# Ready-UNO.net
KiCad netlist of a schematic drawn in EAGLE
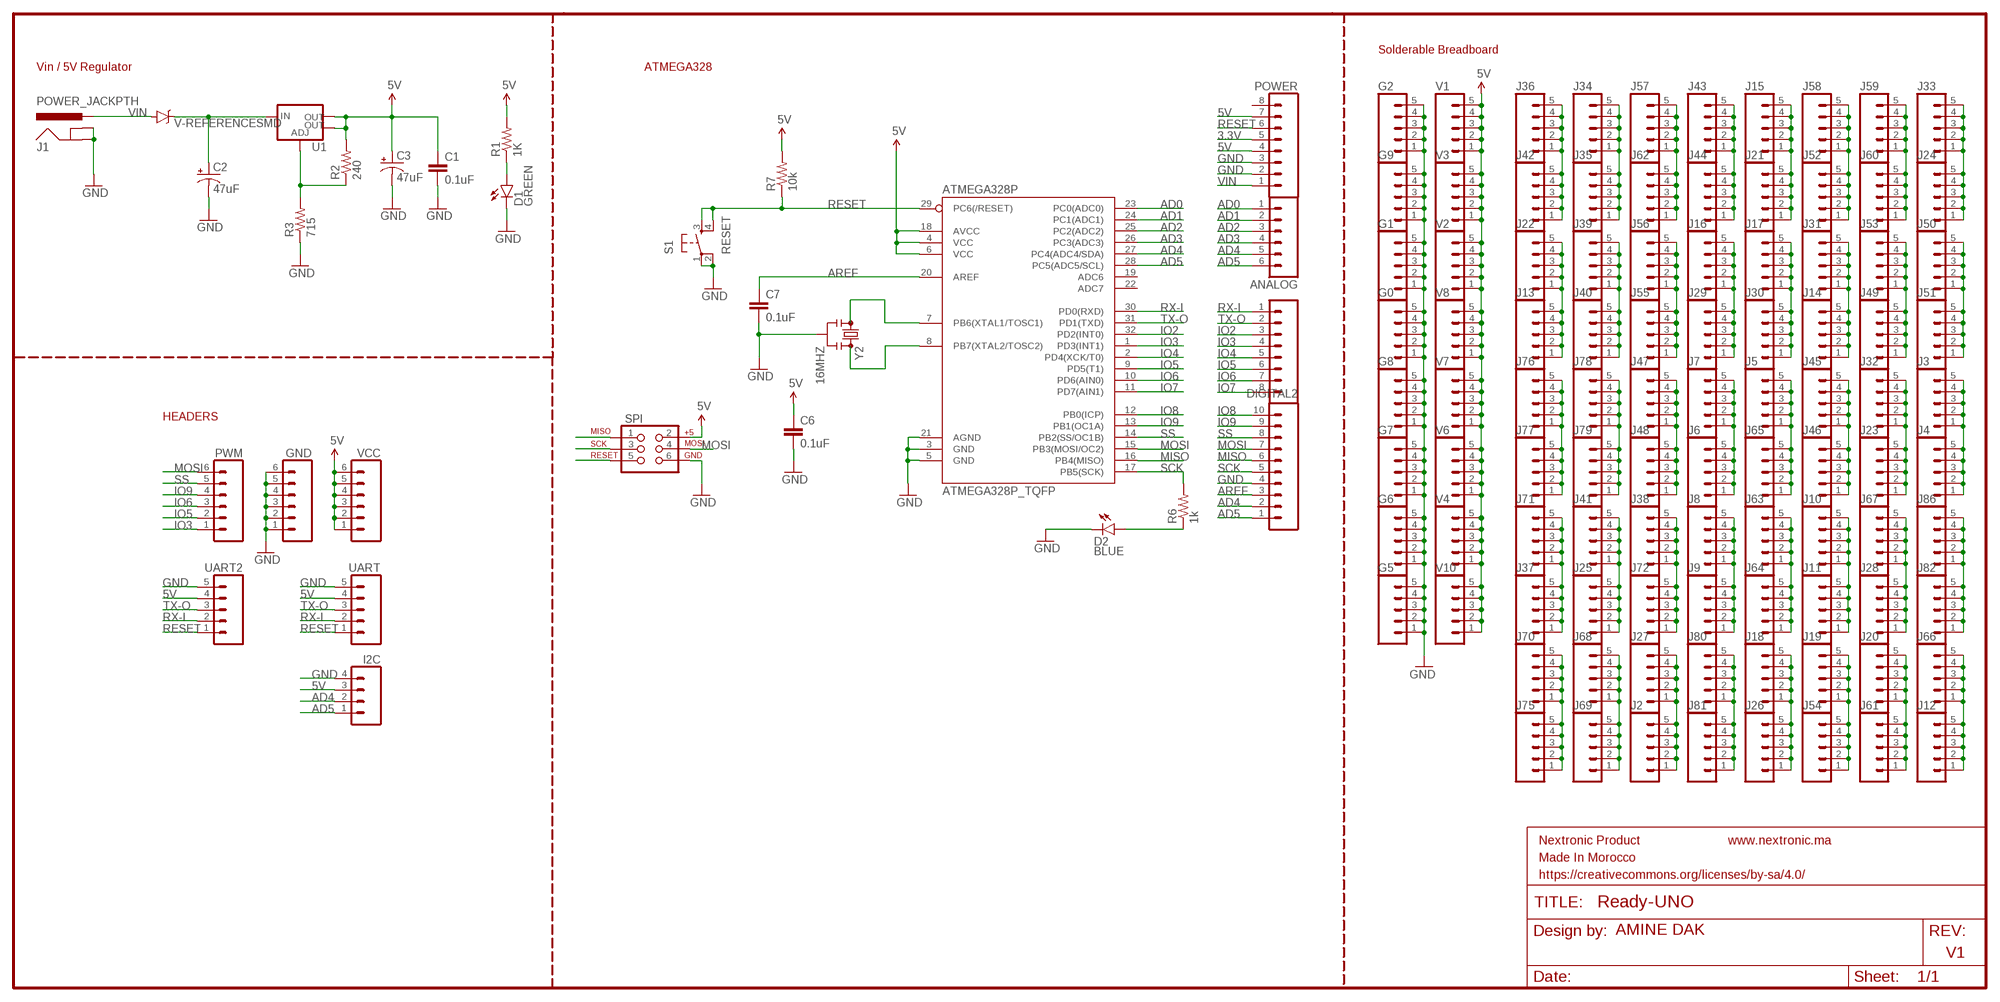
[diagram p0: schematic, sheet 1]

(export (version "E")
  (design (tool "Eeschema 10.0.6"))
  (components
    (comp (ref "ANALOG")
      (value "M06SILK_FEMALE_PTH")
      (footprint "eagle-import:1X06")
      (libsource (lib "eagle-import") (part "M06SILK_FEMALE_PTH"))
    )
    (comp (ref "ATMEGA328P")
      (value "ATMEGA328P_TQFP")
      (footprint "eagle-import:TQFP32-08")
      (libsource (lib "eagle-import") (part "ATMEGA328P_TQFP"))
    )
    (comp (ref "C1")
      (value "0.1uF")
      (footprint "eagle-import:0603-CAP")
      (libsource (lib "eagle-import") (part "CAP0603-CAP"))
    )
    (comp (ref "C2")
      (value "47uF")
      (footprint "eagle-import:PANASONIC_C")
      (libsource (lib "eagle-import") (part "CAP_POLC"))
    )
    (comp (ref "C3")
      (value "47uF")
      (footprint "eagle-import:PANASONIC_C")
      (libsource (lib "eagle-import") (part "CAP_POLC"))
    )
    (comp (ref "C6")
      (value "0.1uF")
      (footprint "eagle-import:0603-CAP")
      (libsource (lib "eagle-import") (part "CAP0603-CAP"))
    )
    (comp (ref "C7")
      (value "0.1uF")
      (footprint "eagle-import:0603-CAP")
      (libsource (lib "eagle-import") (part "CAP0603-CAP"))
    )
    (comp (ref "D1")
      (value "GREEN")
      (footprint "eagle-import:LED-1206")
      (libsource (lib "eagle-import") (part "LED-GREEN1206"))
    )
    (comp (ref "D2")
      (value "BLUE")
      (footprint "eagle-import:LED-1206")
      (libsource (lib "eagle-import") (part "LED-BLUE1206"))
    )
    (comp (ref "DIGITAL")
      (value "M08SILK_FEMALE_PTH")
      (footprint "eagle-import:1X08")
      (libsource (lib "eagle-import") (part "M08SILK_FEMALE_PTH"))
    )
    (comp (ref "DIGITAL2")
      (value "M10SILK_FEMALE_PTH")
      (footprint "eagle-import:1X10")
      (libsource (lib "eagle-import") (part "M10SILK_FEMALE_PTH"))
    )
    (comp (ref "G0")
      (value "M05PTH")
      (footprint "eagle-import:1X05")
      (libsource (lib "eagle-import") (part "M05PTH"))
    )
    (comp (ref "G1")
      (value "M05PTH")
      (footprint "eagle-import:1X05")
      (libsource (lib "eagle-import") (part "M05PTH"))
    )
    (comp (ref "G2")
      (value "M05PTH")
      (footprint "eagle-import:1X05")
      (libsource (lib "eagle-import") (part "M05PTH"))
    )
    (comp (ref "G5")
      (value "M05PTH")
      (footprint "eagle-import:1X05")
      (libsource (lib "eagle-import") (part "M05PTH"))
    )
    (comp (ref "G6")
      (value "M05PTH")
      (footprint "eagle-import:1X05")
      (libsource (lib "eagle-import") (part "M05PTH"))
    )
    (comp (ref "G7")
      (value "M05PTH")
      (footprint "eagle-import:1X05")
      (libsource (lib "eagle-import") (part "M05PTH"))
    )
    (comp (ref "G8")
      (value "M05PTH")
      (footprint "eagle-import:1X05")
      (libsource (lib "eagle-import") (part "M05PTH"))
    )
    (comp (ref "G9")
      (value "M05PTH")
      (footprint "eagle-import:1X05")
      (libsource (lib "eagle-import") (part "M05PTH"))
    )
    (comp (ref "GND")
      (value "M06SILK_FEMALE_PTH")
      (footprint "eagle-import:1X06")
      (libsource (lib "eagle-import") (part "M06SILK_FEMALE_PTH"))
    )
    (comp (ref "I2C")
      (value "M04PTH")
      (footprint "eagle-import:1X04")
      (libsource (lib "eagle-import") (part "M04PTH"))
    )
    (comp (ref "J1")
      (value "POWER_JACKPTH")
      (footprint "eagle-import:POWER_JACK_PTH")
      (libsource (lib "eagle-import") (part "POWER_JACKPTH"))
    )
    (comp (ref "J2")
      (value "M05PTH")
      (footprint "eagle-import:1X05")
      (libsource (lib "eagle-import") (part "M05PTH"))
    )
    (comp (ref "J3")
      (value "M05PTH")
      (footprint "eagle-import:1X05")
      (libsource (lib "eagle-import") (part "M05PTH"))
    )
    (comp (ref "J4")
      (value "M05PTH")
      (footprint "eagle-import:1X05")
      (libsource (lib "eagle-import") (part "M05PTH"))
    )
    (comp (ref "J5")
      (value "M05PTH")
      (footprint "eagle-import:1X05")
      (libsource (lib "eagle-import") (part "M05PTH"))
    )
    (comp (ref "J6")
      (value "M05PTH")
      (footprint "eagle-import:1X05")
      (libsource (lib "eagle-import") (part "M05PTH"))
    )
    (comp (ref "J7")
      (value "M05PTH")
      (footprint "eagle-import:1X05")
      (libsource (lib "eagle-import") (part "M05PTH"))
    )
    (comp (ref "J8")
      (value "M05PTH")
      (footprint "eagle-import:1X05")
      (libsource (lib "eagle-import") (part "M05PTH"))
    )
    (comp (ref "J9")
      (value "M05PTH")
      (footprint "eagle-import:1X05")
      (libsource (lib "eagle-import") (part "M05PTH"))
    )
    (comp (ref "J10")
      (value "M05PTH")
      (footprint "eagle-import:1X05")
      (libsource (lib "eagle-import") (part "M05PTH"))
    )
    (comp (ref "J11")
      (value "M05PTH")
      (footprint "eagle-import:1X05")
      (libsource (lib "eagle-import") (part "M05PTH"))
    )
    (comp (ref "J12")
      (value "M05PTH")
      (footprint "eagle-import:1X05")
      (libsource (lib "eagle-import") (part "M05PTH"))
    )
    (comp (ref "J13")
      (value "M05PTH")
      (footprint "eagle-import:1X05")
      (libsource (lib "eagle-import") (part "M05PTH"))
    )
    (comp (ref "J14")
      (value "M05PTH")
      (footprint "eagle-import:1X05")
      (libsource (lib "eagle-import") (part "M05PTH"))
    )
    (comp (ref "J15")
      (value "M05PTH")
      (footprint "eagle-import:1X05")
      (libsource (lib "eagle-import") (part "M05PTH"))
    )
    (comp (ref "J16")
      (value "M05PTH")
      (footprint "eagle-import:1X05")
      (libsource (lib "eagle-import") (part "M05PTH"))
    )
    (comp (ref "J17")
      (value "M05PTH")
      (footprint "eagle-import:1X05")
      (libsource (lib "eagle-import") (part "M05PTH"))
    )
    (comp (ref "J18")
      (value "M05PTH")
      (footprint "eagle-import:1X05")
      (libsource (lib "eagle-import") (part "M05PTH"))
    )
    (comp (ref "J19")
      (value "M05PTH")
      (footprint "eagle-import:1X05")
      (libsource (lib "eagle-import") (part "M05PTH"))
    )
    (comp (ref "J20")
      (value "M05PTH")
      (footprint "eagle-import:1X05")
      (libsource (lib "eagle-import") (part "M05PTH"))
    )
    (comp (ref "J21")
      (value "M05PTH")
      (footprint "eagle-import:1X05")
      (libsource (lib "eagle-import") (part "M05PTH"))
    )
    (comp (ref "J22")
      (value "M05PTH")
      (footprint "eagle-import:1X05")
      (libsource (lib "eagle-import") (part "M05PTH"))
    )
    (comp (ref "J23")
      (value "M05PTH")
      (footprint "eagle-import:1X05")
      (libsource (lib "eagle-import") (part "M05PTH"))
    )
    (comp (ref "J24")
      (value "M05PTH")
      (footprint "eagle-import:1X05")
      (libsource (lib "eagle-import") (part "M05PTH"))
    )
    (comp (ref "J25")
      (value "M05PTH")
      (footprint "eagle-import:1X05")
      (libsource (lib "eagle-import") (part "M05PTH"))
    )
    (comp (ref "J26")
      (value "M05PTH")
      (footprint "eagle-import:1X05")
      (libsource (lib "eagle-import") (part "M05PTH"))
    )
    (comp (ref "J27")
      (value "M05PTH")
      (footprint "eagle-import:1X05")
      (libsource (lib "eagle-import") (part "M05PTH"))
    )
    (comp (ref "J28")
      (value "M05PTH")
      (footprint "eagle-import:1X05")
      (libsource (lib "eagle-import") (part "M05PTH"))
    )
    (comp (ref "J29")
      (value "M05PTH")
      (footprint "eagle-import:1X05")
      (libsource (lib "eagle-import") (part "M05PTH"))
    )
    (comp (ref "J30")
      (value "M05PTH")
      (footprint "eagle-import:1X05")
      (libsource (lib "eagle-import") (part "M05PTH"))
    )
    (comp (ref "J31")
      (value "M05PTH")
      (footprint "eagle-import:1X05")
      (libsource (lib "eagle-import") (part "M05PTH"))
    )
    (comp (ref "J32")
      (value "M05PTH")
      (footprint "eagle-import:1X05")
      (libsource (lib "eagle-import") (part "M05PTH"))
    )
    (comp (ref "J33")
      (value "M05PTH")
      (footprint "eagle-import:1X05")
      (libsource (lib "eagle-import") (part "M05PTH"))
    )
    (comp (ref "J34")
      (value "M05PTH")
      (footprint "eagle-import:1X05")
      (libsource (lib "eagle-import") (part "M05PTH"))
    )
    (comp (ref "J35")
      (value "M05PTH")
      (footprint "eagle-import:1X05")
      (libsource (lib "eagle-import") (part "M05PTH"))
    )
    (comp (ref "J36")
      (value "M05PTH")
      (footprint "eagle-import:1X05")
      (libsource (lib "eagle-import") (part "M05PTH"))
    )
    (comp (ref "J37")
      (value "M05PTH")
      (footprint "eagle-import:1X05")
      (libsource (lib "eagle-import") (part "M05PTH"))
    )
    (comp (ref "J38")
      (value "M05PTH")
      (footprint "eagle-import:1X05")
      (libsource (lib "eagle-import") (part "M05PTH"))
    )
    (comp (ref "J39")
      (value "M05PTH")
      (footprint "eagle-import:1X05")
      (libsource (lib "eagle-import") (part "M05PTH"))
    )
    (comp (ref "J40")
      (value "M05PTH")
      (footprint "eagle-import:1X05")
      (libsource (lib "eagle-import") (part "M05PTH"))
    )
    (comp (ref "J41")
      (value "M05PTH")
      (footprint "eagle-import:1X05")
      (libsource (lib "eagle-import") (part "M05PTH"))
    )
    (comp (ref "J42")
      (value "M05PTH")
      (footprint "eagle-import:1X05")
      (libsource (lib "eagle-import") (part "M05PTH"))
    )
    (comp (ref "J43")
      (value "M05PTH")
      (footprint "eagle-import:1X05")
      (libsource (lib "eagle-import") (part "M05PTH"))
    )
    (comp (ref "J44")
      (value "M05PTH")
      (footprint "eagle-import:1X05")
      (libsource (lib "eagle-import") (part "M05PTH"))
    )
    (comp (ref "J45")
      (value "M05PTH")
      (footprint "eagle-import:1X05")
      (libsource (lib "eagle-import") (part "M05PTH"))
    )
    (comp (ref "J46")
      (value "M05PTH")
      (footprint "eagle-import:1X05")
      (libsource (lib "eagle-import") (part "M05PTH"))
    )
    (comp (ref "J47")
      (value "M05PTH")
      (footprint "eagle-import:1X05")
      (libsource (lib "eagle-import") (part "M05PTH"))
    )
    (comp (ref "J48")
      (value "M05PTH")
      (footprint "eagle-import:1X05")
      (libsource (lib "eagle-import") (part "M05PTH"))
    )
    (comp (ref "J49")
      (value "M05PTH")
      (footprint "eagle-import:1X05")
      (libsource (lib "eagle-import") (part "M05PTH"))
    )
    (comp (ref "J50")
      (value "M05PTH")
      (footprint "eagle-import:1X05")
      (libsource (lib "eagle-import") (part "M05PTH"))
    )
    (comp (ref "J51")
      (value "M05PTH")
      (footprint "eagle-import:1X05")
      (libsource (lib "eagle-import") (part "M05PTH"))
    )
    (comp (ref "J52")
      (value "M05PTH")
      (footprint "eagle-import:1X05")
      (libsource (lib "eagle-import") (part "M05PTH"))
    )
    (comp (ref "J53")
      (value "M05PTH")
      (footprint "eagle-import:1X05")
      (libsource (lib "eagle-import") (part "M05PTH"))
    )
    (comp (ref "J54")
      (value "M05PTH")
      (footprint "eagle-import:1X05")
      (libsource (lib "eagle-import") (part "M05PTH"))
    )
    (comp (ref "J55")
      (value "M05PTH")
      (footprint "eagle-import:1X05")
      (libsource (lib "eagle-import") (part "M05PTH"))
    )
    (comp (ref "J56")
      (value "M05PTH")
      (footprint "eagle-import:1X05")
      (libsource (lib "eagle-import") (part "M05PTH"))
    )
    (comp (ref "J57")
      (value "M05PTH")
      (footprint "eagle-import:1X05")
      (libsource (lib "eagle-import") (part "M05PTH"))
    )
    (comp (ref "J58")
      (value "M05PTH")
      (footprint "eagle-import:1X05")
      (libsource (lib "eagle-import") (part "M05PTH"))
    )
    (comp (ref "J59")
      (value "M05PTH")
      (footprint "eagle-import:1X05")
      (libsource (lib "eagle-import") (part "M05PTH"))
    )
    (comp (ref "J60")
      (value "M05PTH")
      (footprint "eagle-import:1X05")
      (libsource (lib "eagle-import") (part "M05PTH"))
    )
    (comp (ref "J61")
      (value "M05PTH")
      (footprint "eagle-import:1X05")
      (libsource (lib "eagle-import") (part "M05PTH"))
    )
    (comp (ref "J62")
      (value "M05PTH")
      (footprint "eagle-import:1X05")
      (libsource (lib "eagle-import") (part "M05PTH"))
    )
    (comp (ref "J63")
      (value "M05PTH")
      (footprint "eagle-import:1X05")
      (libsource (lib "eagle-import") (part "M05PTH"))
    )
    (comp (ref "J64")
      (value "M05PTH")
      (footprint "eagle-import:1X05")
      (libsource (lib "eagle-import") (part "M05PTH"))
    )
    (comp (ref "J65")
      (value "M05PTH")
      (footprint "eagle-import:1X05")
      (libsource (lib "eagle-import") (part "M05PTH"))
    )
    (comp (ref "J66")
      (value "M05PTH")
      (footprint "eagle-import:1X05")
      (libsource (lib "eagle-import") (part "M05PTH"))
    )
    (comp (ref "J67")
      (value "M05PTH")
      (footprint "eagle-import:1X05")
      (libsource (lib "eagle-import") (part "M05PTH"))
    )
    (comp (ref "J68")
      (value "M05PTH")
      (footprint "eagle-import:1X05")
      (libsource (lib "eagle-import") (part "M05PTH"))
    )
    (comp (ref "J69")
      (value "M05PTH")
      (footprint "eagle-import:1X05")
      (libsource (lib "eagle-import") (part "M05PTH"))
    )
    (comp (ref "J70")
      (value "M05PTH")
      (footprint "eagle-import:1X05")
      (libsource (lib "eagle-import") (part "M05PTH"))
    )
    (comp (ref "J71")
      (value "M05PTH")
      (footprint "eagle-import:1X05")
      (libsource (lib "eagle-import") (part "M05PTH"))
    )
    (comp (ref "J72")
      (value "M05PTH")
      (footprint "eagle-import:1X05")
      (libsource (lib "eagle-import") (part "M05PTH"))
    )
    (comp (ref "J75")
      (value "M05PTH")
      (footprint "eagle-import:1X05")
      (libsource (lib "eagle-import") (part "M05PTH"))
    )
    (comp (ref "J76")
      (value "M05PTH")
      (footprint "eagle-import:1X05")
      (libsource (lib "eagle-import") (part "M05PTH"))
    )
    (comp (ref "J77")
      (value "M05PTH")
      (footprint "eagle-import:1X05")
      (libsource (lib "eagle-import") (part "M05PTH"))
    )
    (comp (ref "J78")
      (value "M05PTH")
      (footprint "eagle-import:1X05")
      (libsource (lib "eagle-import") (part "M05PTH"))
    )
    (comp (ref "J79")
      (value "M05PTH")
      (footprint "eagle-import:1X05")
      (libsource (lib "eagle-import") (part "M05PTH"))
    )
    (comp (ref "J80")
      (value "M05PTH")
      (footprint "eagle-import:1X05")
      (libsource (lib "eagle-import") (part "M05PTH"))
    )
    (comp (ref "J81")
      (value "M05PTH")
      (footprint "eagle-import:1X05")
      (libsource (lib "eagle-import") (part "M05PTH"))
    )
    (comp (ref "J82")
      (value "M05PTH")
      (footprint "eagle-import:1X05")
      (libsource (lib "eagle-import") (part "M05PTH"))
    )
    (comp (ref "J86")
      (value "M05PTH")
      (footprint "eagle-import:1X05")
      (libsource (lib "eagle-import") (part "M05PTH"))
    )
    (comp (ref "POWER")
      (value "M08SILK_FEMALE_PTH")
      (footprint "eagle-import:1X08")
      (libsource (lib "eagle-import") (part "M08SILK_FEMALE_PTH"))
    )
    (comp (ref "PWM")
      (value "M06SILK_FEMALE_PTH")
      (footprint "eagle-import:1X06")
      (libsource (lib "eagle-import") (part "M06SILK_FEMALE_PTH"))
    )
    (comp (ref "R1")
      (value "1K")
      (footprint "eagle-import:0603-RES")
      (libsource (lib "eagle-import") (part "RESISTOR0603-RES"))
    )
    (comp (ref "R2")
      (value "240")
      (footprint "eagle-import:0603-RES")
      (libsource (lib "eagle-import") (part "RESISTOR0603-RES"))
    )
    (comp (ref "R3")
      (value "715")
      (footprint "eagle-import:0603-RES")
      (libsource (lib "eagle-import") (part "RESISTOR0603-RES"))
    )
    (comp (ref "R6")
      (value "1k")
      (footprint "eagle-import:0603-RES")
      (libsource (lib "eagle-import") (part "RESISTOR0603-RES"))
    )
    (comp (ref "R7")
      (value "10k")
      (footprint "eagle-import:0603-RES")
      (libsource (lib "eagle-import") (part "RESISTOR0603-RES"))
    )
    (comp (ref "S1")
      (value "RESET")
      (footprint "eagle-import:TACTILE-SWITCH-SMD")
      (libsource (lib "eagle-import") (part "TAC_SWITCHSMD"))
    )
    (comp (ref "SPI")
      (value "AVR_SPI_PRG_6NS")
      (footprint "eagle-import:2X3-NS")
      (libsource (lib "eagle-import") (part "AVR_SPI_PRG_6NS"))
    )
    (comp (ref "U$1")
      (value "V-REFERENCESMD")
      (footprint "eagle-import:SOT23-3")
      (libsource (lib "eagle-import") (part "V-REFERENCESMD"))
    )
    (comp (ref "U1")
      (value "V_REG_LM1117SOT223")
      (footprint "eagle-import:SOT223")
      (libsource (lib "eagle-import") (part "V_REG_LM1117SOT223"))
    )
    (comp (ref "UART")
      (value "M05PTH")
      (footprint "eagle-import:1X05")
      (libsource (lib "eagle-import") (part "M05PTH"))
    )
    (comp (ref "UART2")
      (value "M05PTH")
      (footprint "eagle-import:1X05")
      (libsource (lib "eagle-import") (part "M05PTH"))
    )
    (comp (ref "V1")
      (value "M05PTH")
      (footprint "eagle-import:1X05")
      (libsource (lib "eagle-import") (part "M05PTH"))
    )
    (comp (ref "V2")
      (value "M05PTH")
      (footprint "eagle-import:1X05")
      (libsource (lib "eagle-import") (part "M05PTH"))
    )
    (comp (ref "V3")
      (value "M05PTH")
      (footprint "eagle-import:1X05")
      (libsource (lib "eagle-import") (part "M05PTH"))
    )
    (comp (ref "V4")
      (value "M05PTH")
      (footprint "eagle-import:1X05")
      (libsource (lib "eagle-import") (part "M05PTH"))
    )
    (comp (ref "V6")
      (value "M05PTH")
      (footprint "eagle-import:1X05")
      (libsource (lib "eagle-import") (part "M05PTH"))
    )
    (comp (ref "V7")
      (value "M05PTH")
      (footprint "eagle-import:1X05")
      (libsource (lib "eagle-import") (part "M05PTH"))
    )
    (comp (ref "V8")
      (value "M05PTH")
      (footprint "eagle-import:1X05")
      (libsource (lib "eagle-import") (part "M05PTH"))
    )
    (comp (ref "V10")
      (value "M05PTH")
      (footprint "eagle-import:1X05")
      (libsource (lib "eagle-import") (part "M05PTH"))
    )
    (comp (ref "VCC")
      (value "M06SILK_FEMALE_PTH")
      (footprint "eagle-import:1X06")
      (libsource (lib "eagle-import") (part "M06SILK_FEMALE_PTH"))
    )
    (comp (ref "Y2")
      (value "16MHZ")
      (footprint "eagle-import:RESONATOR-SMD")
      (libsource (lib "eagle-import") (part "RESONATOR16MHZ"))
    )
  )
  (nets
    (net (code "1") (name "/3.3V") (class "Default")
      (node (ref "POWER") (pin "5") (pinfunction "5_5") (pintype "passive"))
    )
    (net (code "2") (name "/AD0") (class "Default")
      (node (ref "ANALOG") (pin "1") (pinfunction "1_1") (pintype "passive"))
      (node (ref "ATMEGA328P") (pin "23") (pinfunction "PC0(ADC0)_23") (pintype "bidirectional"))
    )
    (net (code "3") (name "/AD1") (class "Default")
      (node (ref "ANALOG") (pin "2") (pinfunction "2_2") (pintype "passive"))
      (node (ref "ATMEGA328P") (pin "24") (pinfunction "PC1(ADC1)_24") (pintype "bidirectional"))
    )
    (net (code "4") (name "/AD2") (class "Default")
      (node (ref "ANALOG") (pin "3") (pinfunction "3_3") (pintype "passive"))
      (node (ref "ATMEGA328P") (pin "25") (pinfunction "PC2(ADC2)_25") (pintype "bidirectional"))
    )
    (net (code "5") (name "/AD3") (class "Default")
      (node (ref "ANALOG") (pin "4") (pinfunction "4_4") (pintype "passive"))
      (node (ref "ATMEGA328P") (pin "26") (pinfunction "PC3(ADC3)_26") (pintype "bidirectional"))
    )
    (net (code "6") (name "/AD4") (class "Default")
      (node (ref "ANALOG") (pin "5") (pinfunction "5_5") (pintype "passive"))
      (node (ref "ATMEGA328P") (pin "27") (pinfunction "PC4(ADC4/SDA)_27") (pintype "bidirectional"))
      (node (ref "DIGITAL2") (pin "2") (pinfunction "2_2") (pintype "passive"))
      (node (ref "I2C") (pin "2") (pinfunction "2_2") (pintype "passive"))
    )
    (net (code "7") (name "/AD5") (class "Default")
      (node (ref "ANALOG") (pin "6") (pinfunction "6_6") (pintype "passive"))
      (node (ref "ATMEGA328P") (pin "28") (pinfunction "PC5(ADC5/SCL)_28") (pintype "bidirectional"))
      (node (ref "DIGITAL2") (pin "1") (pinfunction "1_1") (pintype "passive"))
      (node (ref "I2C") (pin "1") (pinfunction "1_1") (pintype "passive"))
    )
    (net (code "8") (name "/AREF") (class "Default")
      (node (ref "ATMEGA328P") (pin "20") (pinfunction "AREF_20") (pintype "bidirectional"))
      (node (ref "C7") (pin "1") (pinfunction "1_1") (pintype "passive"))
      (node (ref "DIGITAL2") (pin "3") (pinfunction "3_3") (pintype "passive"))
    )
    (net (code "9") (name "/IO2") (class "Default")
      (node (ref "ATMEGA328P") (pin "32") (pinfunction "PD2(INT0)_32") (pintype "bidirectional"))
      (node (ref "DIGITAL") (pin "3") (pinfunction "3_3") (pintype "passive"))
    )
    (net (code "10") (name "/IO3") (class "Default")
      (node (ref "ATMEGA328P") (pin "1") (pinfunction "PD3(INT1)_1") (pintype "bidirectional"))
      (node (ref "DIGITAL") (pin "4") (pinfunction "4_4") (pintype "passive"))
      (node (ref "PWM") (pin "1") (pinfunction "1_1") (pintype "passive"))
    )
    (net (code "11") (name "/IO4") (class "Default")
      (node (ref "ATMEGA328P") (pin "2") (pinfunction "PD4(XCK/T0)_2") (pintype "bidirectional"))
      (node (ref "DIGITAL") (pin "5") (pinfunction "5_5") (pintype "passive"))
    )
    (net (code "12") (name "/IO5") (class "Default")
      (node (ref "ATMEGA328P") (pin "9") (pinfunction "PD5(T1)_9") (pintype "bidirectional"))
      (node (ref "DIGITAL") (pin "6") (pinfunction "6_6") (pintype "passive"))
      (node (ref "PWM") (pin "2") (pinfunction "2_2") (pintype "passive"))
    )
    (net (code "13") (name "/IO6") (class "Default")
      (node (ref "ATMEGA328P") (pin "10") (pinfunction "PD6(AIN0)_10") (pintype "bidirectional"))
      (node (ref "DIGITAL") (pin "7") (pinfunction "7_7") (pintype "passive"))
      (node (ref "PWM") (pin "3") (pinfunction "3_3") (pintype "passive"))
    )
    (net (code "14") (name "/IO7") (class "Default")
      (node (ref "ATMEGA328P") (pin "11") (pinfunction "PD7(AIN1)_11") (pintype "bidirectional"))
      (node (ref "DIGITAL") (pin "8") (pinfunction "8_8") (pintype "passive"))
    )
    (net (code "15") (name "/IO8") (class "Default")
      (node (ref "ATMEGA328P") (pin "12") (pinfunction "PB0(ICP)_12") (pintype "bidirectional"))
      (node (ref "DIGITAL2") (pin "10") (pinfunction "10_10") (pintype "passive"))
    )
    (net (code "16") (name "/IO9") (class "Default")
      (node (ref "ATMEGA328P") (pin "13") (pinfunction "PB1(OC1A)_13") (pintype "bidirectional"))
      (node (ref "DIGITAL2") (pin "9") (pinfunction "9_9") (pintype "passive"))
      (node (ref "PWM") (pin "4") (pinfunction "4_4") (pintype "passive"))
    )
    (net (code "17") (name "/MISO") (class "Default")
      (node (ref "ATMEGA328P") (pin "16") (pinfunction "PB4(MISO)_16") (pintype "bidirectional"))
      (node (ref "DIGITAL2") (pin "6") (pinfunction "6_6") (pintype "passive"))
      (node (ref "SPI") (pin "1") (pinfunction "1_1") (pintype "passive"))
    )
    (net (code "18") (name "/MOSI") (class "Default")
      (node (ref "ATMEGA328P") (pin "15") (pinfunction "PB3(MOSI/OC2)_15") (pintype "bidirectional"))
      (node (ref "DIGITAL2") (pin "7") (pinfunction "7_7") (pintype "passive"))
      (node (ref "PWM") (pin "6") (pinfunction "6_6") (pintype "passive"))
      (node (ref "SPI") (pin "4") (pinfunction "4_4") (pintype "passive"))
    )
    (net (code "19") (name "/RESET") (class "Default")
      (node (ref "ATMEGA328P") (pin "29") (pinfunction "PC6(/RESET)_29") (pintype "bidirectional"))
      (node (ref "POWER") (pin "6") (pinfunction "6_6") (pintype "passive"))
      (node (ref "R7") (pin "1") (pinfunction "1_1") (pintype "passive"))
      (node (ref "S1") (pin "3") (pinfunction "3_3") (pintype "passive"))
      (node (ref "S1") (pin "4") (pinfunction "4_4") (pintype "passive"))
      (node (ref "SPI") (pin "5") (pinfunction "5_5") (pintype "passive"))
      (node (ref "UART") (pin "1") (pinfunction "1_1") (pintype "passive"))
      (node (ref "UART2") (pin "1") (pinfunction "1_1") (pintype "passive"))
    )
    (net (code "20") (name "/RX-I") (class "Default")
      (node (ref "ATMEGA328P") (pin "30") (pinfunction "PD0(RXD)_30") (pintype "bidirectional"))
      (node (ref "DIGITAL") (pin "1") (pinfunction "1_1") (pintype "passive"))
      (node (ref "UART") (pin "2") (pinfunction "2_2") (pintype "passive"))
      (node (ref "UART2") (pin "2") (pinfunction "2_2") (pintype "passive"))
    )
    (net (code "21") (name "/SCK") (class "Default")
      (node (ref "ATMEGA328P") (pin "17") (pinfunction "PB5(SCK)_17") (pintype "bidirectional"))
      (node (ref "DIGITAL2") (pin "5") (pinfunction "5_5") (pintype "passive"))
      (node (ref "R6") (pin "2") (pinfunction "2_2") (pintype "passive"))
      (node (ref "SPI") (pin "3") (pinfunction "3_3") (pintype "passive"))
    )
    (net (code "22") (name "/SS") (class "Default")
      (node (ref "ATMEGA328P") (pin "14") (pinfunction "PB2(SS/OC1B)_14") (pintype "bidirectional"))
      (node (ref "DIGITAL2") (pin "8") (pinfunction "8_8") (pintype "passive"))
      (node (ref "PWM") (pin "5") (pinfunction "5_5") (pintype "passive"))
    )
    (net (code "23") (name "/TX-O") (class "Default")
      (node (ref "ATMEGA328P") (pin "31") (pinfunction "PD1(TXD)_31") (pintype "bidirectional"))
      (node (ref "DIGITAL") (pin "2") (pinfunction "2_2") (pintype "passive"))
      (node (ref "UART") (pin "3") (pinfunction "3_3") (pintype "passive"))
      (node (ref "UART2") (pin "3") (pinfunction "3_3") (pintype "passive"))
    )
    (net (code "24") (name "/VIN") (class "Default")
      (node (ref "J1") (pin "PWR") (pinfunction "PWR_PWR") (pintype "bidirectional"))
      (node (ref "POWER") (pin "1") (pinfunction "1_1") (pintype "passive"))
      (node (ref "U$1") (pin "2") (pinfunction "A_2") (pintype "passive"))
    )
    (net (code "25") (name "5V") (class "Default")
      (node (ref "ATMEGA328P") (pin "18") (pinfunction "AVCC_18") (pintype "bidirectional"))
      (node (ref "ATMEGA328P") (pin "4") (pinfunction "VCC_4") (pintype "bidirectional"))
      (node (ref "ATMEGA328P") (pin "6") (pinfunction "VCC_6") (pintype "bidirectional"))
      (node (ref "C1") (pin "1") (pinfunction "1_1") (pintype "passive"))
      (node (ref "C3") (pin "+") (pinfunction "+_+") (pintype "passive"))
      (node (ref "C6") (pin "1") (pinfunction "1_1") (pintype "passive"))
      (node (ref "I2C") (pin "3") (pinfunction "3_3") (pintype "passive"))
      (node (ref "POWER") (pin "4") (pinfunction "4_4") (pintype "passive"))
      (node (ref "POWER") (pin "7") (pinfunction "7_7") (pintype "passive"))
      (node (ref "R1") (pin "2") (pinfunction "2_2") (pintype "passive"))
      (node (ref "R2") (pin "2") (pinfunction "2_2") (pintype "passive"))
      (node (ref "R7") (pin "2") (pinfunction "2_2") (pintype "passive"))
      (node (ref "SPI") (pin "2") (pinfunction "2_2") (pintype "passive"))
      (node (ref "U1") (pin "2") (pinfunction "OUT_2") (pintype "output"))
      (node (ref "U1") (pin "4") (pinfunction "OUT_4") (pintype "output"))
      (node (ref "UART") (pin "4") (pinfunction "4_4") (pintype "passive"))
      (node (ref "UART2") (pin "4") (pinfunction "4_4") (pintype "passive"))
      (node (ref "V1") (pin "1") (pinfunction "1_1") (pintype "passive"))
      (node (ref "V1") (pin "2") (pinfunction "2_2") (pintype "passive"))
      (node (ref "V1") (pin "3") (pinfunction "3_3") (pintype "passive"))
      (node (ref "V1") (pin "4") (pinfunction "4_4") (pintype "passive"))
      (node (ref "V1") (pin "5") (pinfunction "5_5") (pintype "passive"))
      (node (ref "V10") (pin "1") (pinfunction "1_1") (pintype "passive"))
      (node (ref "V10") (pin "2") (pinfunction "2_2") (pintype "passive"))
      (node (ref "V10") (pin "3") (pinfunction "3_3") (pintype "passive"))
      (node (ref "V10") (pin "4") (pinfunction "4_4") (pintype "passive"))
      (node (ref "V10") (pin "5") (pinfunction "5_5") (pintype "passive"))
      (node (ref "V2") (pin "1") (pinfunction "1_1") (pintype "passive"))
      (node (ref "V2") (pin "2") (pinfunction "2_2") (pintype "passive"))
      (node (ref "V2") (pin "3") (pinfunction "3_3") (pintype "passive"))
      (node (ref "V2") (pin "4") (pinfunction "4_4") (pintype "passive"))
      (node (ref "V2") (pin "5") (pinfunction "5_5") (pintype "passive"))
      (node (ref "V3") (pin "1") (pinfunction "1_1") (pintype "passive"))
      (node (ref "V3") (pin "2") (pinfunction "2_2") (pintype "passive"))
      (node (ref "V3") (pin "3") (pinfunction "3_3") (pintype "passive"))
      (node (ref "V3") (pin "4") (pinfunction "4_4") (pintype "passive"))
      (node (ref "V3") (pin "5") (pinfunction "5_5") (pintype "passive"))
      (node (ref "V4") (pin "1") (pinfunction "1_1") (pintype "passive"))
      (node (ref "V4") (pin "2") (pinfunction "2_2") (pintype "passive"))
      (node (ref "V4") (pin "3") (pinfunction "3_3") (pintype "passive"))
      (node (ref "V4") (pin "4") (pinfunction "4_4") (pintype "passive"))
      (node (ref "V4") (pin "5") (pinfunction "5_5") (pintype "passive"))
      (node (ref "V6") (pin "1") (pinfunction "1_1") (pintype "passive"))
      (node (ref "V6") (pin "2") (pinfunction "2_2") (pintype "passive"))
      (node (ref "V6") (pin "3") (pinfunction "3_3") (pintype "passive"))
      (node (ref "V6") (pin "4") (pinfunction "4_4") (pintype "passive"))
      (node (ref "V6") (pin "5") (pinfunction "5_5") (pintype "passive"))
      (node (ref "V7") (pin "1") (pinfunction "1_1") (pintype "passive"))
      (node (ref "V7") (pin "2") (pinfunction "2_2") (pintype "passive"))
      (node (ref "V7") (pin "3") (pinfunction "3_3") (pintype "passive"))
      (node (ref "V7") (pin "4") (pinfunction "4_4") (pintype "passive"))
      (node (ref "V7") (pin "5") (pinfunction "5_5") (pintype "passive"))
      (node (ref "V8") (pin "1") (pinfunction "1_1") (pintype "passive"))
      (node (ref "V8") (pin "2") (pinfunction "2_2") (pintype "passive"))
      (node (ref "V8") (pin "3") (pinfunction "3_3") (pintype "passive"))
      (node (ref "V8") (pin "4") (pinfunction "4_4") (pintype "passive"))
      (node (ref "V8") (pin "5") (pinfunction "5_5") (pintype "passive"))
      (node (ref "VCC") (pin "1") (pinfunction "1_1") (pintype "passive"))
      (node (ref "VCC") (pin "2") (pinfunction "2_2") (pintype "passive"))
      (node (ref "VCC") (pin "3") (pinfunction "3_3") (pintype "passive"))
      (node (ref "VCC") (pin "4") (pinfunction "4_4") (pintype "passive"))
      (node (ref "VCC") (pin "5") (pinfunction "5_5") (pintype "passive"))
      (node (ref "VCC") (pin "6") (pinfunction "6_6") (pintype "passive"))
    )
    (net (code "26") (name "GND") (class "Default")
      (node (ref "ATMEGA328P") (pin "21") (pinfunction "AGND_21") (pintype "bidirectional"))
      (node (ref "ATMEGA328P") (pin "3") (pinfunction "GND_3") (pintype "bidirectional"))
      (node (ref "ATMEGA328P") (pin "5") (pinfunction "GND_5") (pintype "bidirectional"))
      (node (ref "C1") (pin "2") (pinfunction "2_2") (pintype "passive"))
      (node (ref "C2") (pin "-") (pinfunction "-_-") (pintype "passive"))
      (node (ref "C3") (pin "-") (pinfunction "-_-") (pintype "passive"))
      (node (ref "C6") (pin "2") (pinfunction "2_2") (pintype "passive"))
      (node (ref "C7") (pin "2") (pinfunction "2_2") (pintype "passive"))
      (node (ref "D1") (pin "C") (pinfunction "C_C") (pintype "passive"))
      (node (ref "D2") (pin "C") (pinfunction "C_C") (pintype "passive"))
      (node (ref "DIGITAL2") (pin "4") (pinfunction "4_4") (pintype "passive"))
      (node (ref "G0") (pin "1") (pinfunction "1_1") (pintype "passive"))
      (node (ref "G0") (pin "2") (pinfunction "2_2") (pintype "passive"))
      (node (ref "G0") (pin "3") (pinfunction "3_3") (pintype "passive"))
      (node (ref "G0") (pin "4") (pinfunction "4_4") (pintype "passive"))
      (node (ref "G0") (pin "5") (pinfunction "5_5") (pintype "passive"))
      (node (ref "G1") (pin "1") (pinfunction "1_1") (pintype "passive"))
      (node (ref "G1") (pin "2") (pinfunction "2_2") (pintype "passive"))
      (node (ref "G1") (pin "3") (pinfunction "3_3") (pintype "passive"))
      (node (ref "G1") (pin "4") (pinfunction "4_4") (pintype "passive"))
      (node (ref "G1") (pin "5") (pinfunction "5_5") (pintype "passive"))
      (node (ref "G2") (pin "1") (pinfunction "1_1") (pintype "passive"))
      (node (ref "G2") (pin "2") (pinfunction "2_2") (pintype "passive"))
      (node (ref "G2") (pin "3") (pinfunction "3_3") (pintype "passive"))
      (node (ref "G2") (pin "4") (pinfunction "4_4") (pintype "passive"))
      (node (ref "G2") (pin "5") (pinfunction "5_5") (pintype "passive"))
      (node (ref "G5") (pin "1") (pinfunction "1_1") (pintype "passive"))
      (node (ref "G5") (pin "2") (pinfunction "2_2") (pintype "passive"))
      (node (ref "G5") (pin "3") (pinfunction "3_3") (pintype "passive"))
      (node (ref "G5") (pin "4") (pinfunction "4_4") (pintype "passive"))
      (node (ref "G5") (pin "5") (pinfunction "5_5") (pintype "passive"))
      (node (ref "G6") (pin "1") (pinfunction "1_1") (pintype "passive"))
      (node (ref "G6") (pin "2") (pinfunction "2_2") (pintype "passive"))
      (node (ref "G6") (pin "3") (pinfunction "3_3") (pintype "passive"))
      (node (ref "G6") (pin "4") (pinfunction "4_4") (pintype "passive"))
      (node (ref "G6") (pin "5") (pinfunction "5_5") (pintype "passive"))
      (node (ref "G7") (pin "1") (pinfunction "1_1") (pintype "passive"))
      (node (ref "G7") (pin "2") (pinfunction "2_2") (pintype "passive"))
      (node (ref "G7") (pin "3") (pinfunction "3_3") (pintype "passive"))
      (node (ref "G7") (pin "4") (pinfunction "4_4") (pintype "passive"))
      (node (ref "G7") (pin "5") (pinfunction "5_5") (pintype "passive"))
      (node (ref "G8") (pin "1") (pinfunction "1_1") (pintype "passive"))
      (node (ref "G8") (pin "2") (pinfunction "2_2") (pintype "passive"))
      (node (ref "G8") (pin "3") (pinfunction "3_3") (pintype "passive"))
      (node (ref "G8") (pin "4") (pinfunction "4_4") (pintype "passive"))
      (node (ref "G8") (pin "5") (pinfunction "5_5") (pintype "passive"))
      (node (ref "G9") (pin "1") (pinfunction "1_1") (pintype "passive"))
      (node (ref "G9") (pin "2") (pinfunction "2_2") (pintype "passive"))
      (node (ref "G9") (pin "3") (pinfunction "3_3") (pintype "passive"))
      (node (ref "G9") (pin "4") (pinfunction "4_4") (pintype "passive"))
      (node (ref "G9") (pin "5") (pinfunction "5_5") (pintype "passive"))
      (node (ref "GND") (pin "1") (pinfunction "1_1") (pintype "passive"))
      (node (ref "GND") (pin "2") (pinfunction "2_2") (pintype "passive"))
      (node (ref "GND") (pin "3") (pinfunction "3_3") (pintype "passive"))
      (node (ref "GND") (pin "4") (pinfunction "4_4") (pintype "passive"))
      (node (ref "GND") (pin "5") (pinfunction "5_5") (pintype "passive"))
      (node (ref "GND") (pin "6") (pinfunction "6_6") (pintype "passive"))
      (node (ref "I2C") (pin "4") (pinfunction "4_4") (pintype "passive"))
      (node (ref "J1") (pin "GND") (pinfunction "GND_GND") (pintype "bidirectional"))
      (node (ref "J1") (pin "GNDBREAK") (pinfunction "GNDBREAK_GNDBREAK") (pintype "bidirectional"))
      (node (ref "POWER") (pin "2") (pinfunction "2_2") (pintype "passive"))
      (node (ref "POWER") (pin "3") (pinfunction "3_3") (pintype "passive"))
      (node (ref "R3") (pin "1") (pinfunction "1_1") (pintype "passive"))
      (node (ref "S1") (pin "1") (pinfunction "1_1") (pintype "passive"))
      (node (ref "S1") (pin "2") (pinfunction "2_2") (pintype "passive"))
      (node (ref "SPI") (pin "6") (pinfunction "6_6") (pintype "passive"))
      (node (ref "UART") (pin "5") (pinfunction "5_5") (pintype "passive"))
      (node (ref "UART2") (pin "5") (pinfunction "5_5") (pintype "passive"))
      (node (ref "Y2") (pin "2") (pinfunction "2_2") (pintype "passive"))
    )
    (net (code "27") (name "Net-(ATMEGA328P-PB6(XTAL1{slash}TOSC1))") (class "Default")
      (node (ref "ATMEGA328P") (pin "7") (pinfunction "PB6(XTAL1/TOSC1)_7") (pintype "bidirectional"))
      (node (ref "Y2") (pin "1") (pinfunction "1_1") (pintype "passive"))
    )
    (net (code "28") (name "Net-(ATMEGA328P-PB7(XTAL2{slash}TOSC2))") (class "Default")
      (node (ref "ATMEGA328P") (pin "8") (pinfunction "PB7(XTAL2/TOSC2)_8") (pintype "bidirectional"))
      (node (ref "Y2") (pin "3") (pinfunction "3_3") (pintype "passive"))
    )
    (net (code "29") (name "Net-(D1-PadA)") (class "Default")
      (node (ref "D1") (pin "A") (pinfunction "A_A") (pintype "passive"))
      (node (ref "R1") (pin "1") (pinfunction "1_1") (pintype "passive"))
    )
    (net (code "30") (name "Net-(D2-PadA)") (class "Default")
      (node (ref "D2") (pin "A") (pinfunction "A_A") (pintype "passive"))
      (node (ref "R6") (pin "1") (pinfunction "1_1") (pintype "passive"))
    )
    (net (code "31") (name "Net-(J2-Pad1)") (class "Default")
      (node (ref "J2") (pin "1") (pinfunction "1_1") (pintype "passive"))
      (node (ref "J2") (pin "2") (pinfunction "2_2") (pintype "passive"))
      (node (ref "J2") (pin "3") (pinfunction "3_3") (pintype "passive"))
      (node (ref "J2") (pin "4") (pinfunction "4_4") (pintype "passive"))
      (node (ref "J2") (pin "5") (pinfunction "5_5") (pintype "passive"))
      (node (ref "J27") (pin "1") (pinfunction "1_1") (pintype "passive"))
      (node (ref "J27") (pin "2") (pinfunction "2_2") (pintype "passive"))
      (node (ref "J27") (pin "3") (pinfunction "3_3") (pintype "passive"))
      (node (ref "J27") (pin "4") (pinfunction "4_4") (pintype "passive"))
      (node (ref "J27") (pin "5") (pinfunction "5_5") (pintype "passive"))
    )
    (net (code "32") (name "Net-(J3-Pad1)") (class "Default")
      (node (ref "J3") (pin "1") (pinfunction "1_1") (pintype "passive"))
      (node (ref "J3") (pin "2") (pinfunction "2_2") (pintype "passive"))
      (node (ref "J3") (pin "3") (pinfunction "3_3") (pintype "passive"))
      (node (ref "J3") (pin "4") (pinfunction "4_4") (pintype "passive"))
      (node (ref "J3") (pin "5") (pinfunction "5_5") (pintype "passive"))
      (node (ref "J4") (pin "1") (pinfunction "1_1") (pintype "passive"))
      (node (ref "J4") (pin "2") (pinfunction "2_2") (pintype "passive"))
      (node (ref "J4") (pin "3") (pinfunction "3_3") (pintype "passive"))
      (node (ref "J4") (pin "4") (pinfunction "4_4") (pintype "passive"))
      (node (ref "J4") (pin "5") (pinfunction "5_5") (pintype "passive"))
    )
    (net (code "33") (name "Net-(J5-Pad1)") (class "Default")
      (node (ref "J5") (pin "1") (pinfunction "1_1") (pintype "passive"))
      (node (ref "J5") (pin "2") (pinfunction "2_2") (pintype "passive"))
      (node (ref "J5") (pin "3") (pinfunction "3_3") (pintype "passive"))
      (node (ref "J5") (pin "4") (pinfunction "4_4") (pintype "passive"))
      (node (ref "J5") (pin "5") (pinfunction "5_5") (pintype "passive"))
      (node (ref "J65") (pin "1") (pinfunction "1_1") (pintype "passive"))
      (node (ref "J65") (pin "2") (pinfunction "2_2") (pintype "passive"))
      (node (ref "J65") (pin "3") (pinfunction "3_3") (pintype "passive"))
      (node (ref "J65") (pin "4") (pinfunction "4_4") (pintype "passive"))
      (node (ref "J65") (pin "5") (pinfunction "5_5") (pintype "passive"))
    )
    (net (code "34") (name "Net-(J6-Pad1)") (class "Default")
      (node (ref "J6") (pin "1") (pinfunction "1_1") (pintype "passive"))
      (node (ref "J6") (pin "2") (pinfunction "2_2") (pintype "passive"))
      (node (ref "J6") (pin "3") (pinfunction "3_3") (pintype "passive"))
      (node (ref "J6") (pin "4") (pinfunction "4_4") (pintype "passive"))
      (node (ref "J6") (pin "5") (pinfunction "5_5") (pintype "passive"))
      (node (ref "J7") (pin "1") (pinfunction "1_1") (pintype "passive"))
      (node (ref "J7") (pin "2") (pinfunction "2_2") (pintype "passive"))
      (node (ref "J7") (pin "3") (pinfunction "3_3") (pintype "passive"))
      (node (ref "J7") (pin "4") (pinfunction "4_4") (pintype "passive"))
      (node (ref "J7") (pin "5") (pinfunction "5_5") (pintype "passive"))
    )
    (net (code "35") (name "Net-(J8-Pad1)") (class "Default")
      (node (ref "J8") (pin "1") (pinfunction "1_1") (pintype "passive"))
      (node (ref "J8") (pin "2") (pinfunction "2_2") (pintype "passive"))
      (node (ref "J8") (pin "3") (pinfunction "3_3") (pintype "passive"))
      (node (ref "J8") (pin "4") (pinfunction "4_4") (pintype "passive"))
      (node (ref "J8") (pin "5") (pinfunction "5_5") (pintype "passive"))
      (node (ref "J9") (pin "1") (pinfunction "1_1") (pintype "passive"))
      (node (ref "J9") (pin "2") (pinfunction "2_2") (pintype "passive"))
      (node (ref "J9") (pin "3") (pinfunction "3_3") (pintype "passive"))
      (node (ref "J9") (pin "4") (pinfunction "4_4") (pintype "passive"))
      (node (ref "J9") (pin "5") (pinfunction "5_5") (pintype "passive"))
    )
    (net (code "36") (name "Net-(J10-Pad1)") (class "Default")
      (node (ref "J10") (pin "1") (pinfunction "1_1") (pintype "passive"))
      (node (ref "J10") (pin "2") (pinfunction "2_2") (pintype "passive"))
      (node (ref "J10") (pin "3") (pinfunction "3_3") (pintype "passive"))
      (node (ref "J10") (pin "4") (pinfunction "4_4") (pintype "passive"))
      (node (ref "J10") (pin "5") (pinfunction "5_5") (pintype "passive"))
      (node (ref "J11") (pin "1") (pinfunction "1_1") (pintype "passive"))
      (node (ref "J11") (pin "2") (pinfunction "2_2") (pintype "passive"))
      (node (ref "J11") (pin "3") (pinfunction "3_3") (pintype "passive"))
      (node (ref "J11") (pin "4") (pinfunction "4_4") (pintype "passive"))
      (node (ref "J11") (pin "5") (pinfunction "5_5") (pintype "passive"))
    )
    (net (code "37") (name "Net-(J12-Pad1)") (class "Default")
      (node (ref "J12") (pin "1") (pinfunction "1_1") (pintype "passive"))
      (node (ref "J12") (pin "2") (pinfunction "2_2") (pintype "passive"))
      (node (ref "J12") (pin "3") (pinfunction "3_3") (pintype "passive"))
      (node (ref "J12") (pin "4") (pinfunction "4_4") (pintype "passive"))
      (node (ref "J12") (pin "5") (pinfunction "5_5") (pintype "passive"))
      (node (ref "J66") (pin "1") (pinfunction "1_1") (pintype "passive"))
      (node (ref "J66") (pin "2") (pinfunction "2_2") (pintype "passive"))
      (node (ref "J66") (pin "3") (pinfunction "3_3") (pintype "passive"))
      (node (ref "J66") (pin "4") (pinfunction "4_4") (pintype "passive"))
      (node (ref "J66") (pin "5") (pinfunction "5_5") (pintype "passive"))
    )
    (net (code "38") (name "Net-(J13-Pad1)") (class "Default")
      (node (ref "J13") (pin "1") (pinfunction "1_1") (pintype "passive"))
      (node (ref "J13") (pin "2") (pinfunction "2_2") (pintype "passive"))
      (node (ref "J13") (pin "3") (pinfunction "3_3") (pintype "passive"))
      (node (ref "J13") (pin "4") (pinfunction "4_4") (pintype "passive"))
      (node (ref "J13") (pin "5") (pinfunction "5_5") (pintype "passive"))
      (node (ref "J22") (pin "1") (pinfunction "1_1") (pintype "passive"))
      (node (ref "J22") (pin "2") (pinfunction "2_2") (pintype "passive"))
      (node (ref "J22") (pin "3") (pinfunction "3_3") (pintype "passive"))
      (node (ref "J22") (pin "4") (pinfunction "4_4") (pintype "passive"))
      (node (ref "J22") (pin "5") (pinfunction "5_5") (pintype "passive"))
    )
    (net (code "39") (name "Net-(J14-Pad1)") (class "Default")
      (node (ref "J14") (pin "1") (pinfunction "1_1") (pintype "passive"))
      (node (ref "J14") (pin "2") (pinfunction "2_2") (pintype "passive"))
      (node (ref "J14") (pin "3") (pinfunction "3_3") (pintype "passive"))
      (node (ref "J14") (pin "4") (pinfunction "4_4") (pintype "passive"))
      (node (ref "J14") (pin "5") (pinfunction "5_5") (pintype "passive"))
      (node (ref "J31") (pin "1") (pinfunction "1_1") (pintype "passive"))
      (node (ref "J31") (pin "2") (pinfunction "2_2") (pintype "passive"))
      (node (ref "J31") (pin "3") (pinfunction "3_3") (pintype "passive"))
      (node (ref "J31") (pin "4") (pinfunction "4_4") (pintype "passive"))
      (node (ref "J31") (pin "5") (pinfunction "5_5") (pintype "passive"))
    )
    (net (code "40") (name "Net-(J15-Pad1)") (class "Default")
      (node (ref "J15") (pin "1") (pinfunction "1_1") (pintype "passive"))
      (node (ref "J15") (pin "2") (pinfunction "2_2") (pintype "passive"))
      (node (ref "J15") (pin "3") (pinfunction "3_3") (pintype "passive"))
      (node (ref "J15") (pin "4") (pinfunction "4_4") (pintype "passive"))
      (node (ref "J15") (pin "5") (pinfunction "5_5") (pintype "passive"))
      (node (ref "J21") (pin "1") (pinfunction "1_1") (pintype "passive"))
      (node (ref "J21") (pin "2") (pinfunction "2_2") (pintype "passive"))
      (node (ref "J21") (pin "3") (pinfunction "3_3") (pintype "passive"))
      (node (ref "J21") (pin "4") (pinfunction "4_4") (pintype "passive"))
      (node (ref "J21") (pin "5") (pinfunction "5_5") (pintype "passive"))
    )
    (net (code "41") (name "Net-(J16-Pad1)") (class "Default")
      (node (ref "J16") (pin "1") (pinfunction "1_1") (pintype "passive"))
      (node (ref "J16") (pin "2") (pinfunction "2_2") (pintype "passive"))
      (node (ref "J16") (pin "3") (pinfunction "3_3") (pintype "passive"))
      (node (ref "J16") (pin "4") (pinfunction "4_4") (pintype "passive"))
      (node (ref "J16") (pin "5") (pinfunction "5_5") (pintype "passive"))
      (node (ref "J29") (pin "1") (pinfunction "1_1") (pintype "passive"))
      (node (ref "J29") (pin "2") (pinfunction "2_2") (pintype "passive"))
      (node (ref "J29") (pin "3") (pinfunction "3_3") (pintype "passive"))
      (node (ref "J29") (pin "4") (pinfunction "4_4") (pintype "passive"))
      (node (ref "J29") (pin "5") (pinfunction "5_5") (pintype "passive"))
    )
    (net (code "42") (name "Net-(J17-Pad1)") (class "Default")
      (node (ref "J17") (pin "1") (pinfunction "1_1") (pintype "passive"))
      (node (ref "J17") (pin "2") (pinfunction "2_2") (pintype "passive"))
      (node (ref "J17") (pin "3") (pinfunction "3_3") (pintype "passive"))
      (node (ref "J17") (pin "4") (pinfunction "4_4") (pintype "passive"))
      (node (ref "J17") (pin "5") (pinfunction "5_5") (pintype "passive"))
      (node (ref "J30") (pin "1") (pinfunction "1_1") (pintype "passive"))
      (node (ref "J30") (pin "2") (pinfunction "2_2") (pintype "passive"))
      (node (ref "J30") (pin "3") (pinfunction "3_3") (pintype "passive"))
      (node (ref "J30") (pin "4") (pinfunction "4_4") (pintype "passive"))
      (node (ref "J30") (pin "5") (pinfunction "5_5") (pintype "passive"))
    )
    (net (code "43") (name "Net-(J18-Pad1)") (class "Default")
      (node (ref "J18") (pin "1") (pinfunction "1_1") (pintype "passive"))
      (node (ref "J18") (pin "2") (pinfunction "2_2") (pintype "passive"))
      (node (ref "J18") (pin "3") (pinfunction "3_3") (pintype "passive"))
      (node (ref "J18") (pin "4") (pinfunction "4_4") (pintype "passive"))
      (node (ref "J18") (pin "5") (pinfunction "5_5") (pintype "passive"))
      (node (ref "J26") (pin "1") (pinfunction "1_1") (pintype "passive"))
      (node (ref "J26") (pin "2") (pinfunction "2_2") (pintype "passive"))
      (node (ref "J26") (pin "3") (pinfunction "3_3") (pintype "passive"))
      (node (ref "J26") (pin "4") (pinfunction "4_4") (pintype "passive"))
      (node (ref "J26") (pin "5") (pinfunction "5_5") (pintype "passive"))
    )
    (net (code "44") (name "Net-(J19-Pad1)") (class "Default")
      (node (ref "J19") (pin "1") (pinfunction "1_1") (pintype "passive"))
      (node (ref "J19") (pin "2") (pinfunction "2_2") (pintype "passive"))
      (node (ref "J19") (pin "3") (pinfunction "3_3") (pintype "passive"))
      (node (ref "J19") (pin "4") (pinfunction "4_4") (pintype "passive"))
      (node (ref "J19") (pin "5") (pinfunction "5_5") (pintype "passive"))
      (node (ref "J54") (pin "1") (pinfunction "1_1") (pintype "passive"))
      (node (ref "J54") (pin "2") (pinfunction "2_2") (pintype "passive"))
      (node (ref "J54") (pin "3") (pinfunction "3_3") (pintype "passive"))
      (node (ref "J54") (pin "4") (pinfunction "4_4") (pintype "passive"))
      (node (ref "J54") (pin "5") (pinfunction "5_5") (pintype "passive"))
    )
    (net (code "45") (name "Net-(J20-Pad1)") (class "Default")
      (node (ref "J20") (pin "1") (pinfunction "1_1") (pintype "passive"))
      (node (ref "J20") (pin "2") (pinfunction "2_2") (pintype "passive"))
      (node (ref "J20") (pin "3") (pinfunction "3_3") (pintype "passive"))
      (node (ref "J20") (pin "4") (pinfunction "4_4") (pintype "passive"))
      (node (ref "J20") (pin "5") (pinfunction "5_5") (pintype "passive"))
      (node (ref "J61") (pin "1") (pinfunction "1_1") (pintype "passive"))
      (node (ref "J61") (pin "2") (pinfunction "2_2") (pintype "passive"))
      (node (ref "J61") (pin "3") (pinfunction "3_3") (pintype "passive"))
      (node (ref "J61") (pin "4") (pinfunction "4_4") (pintype "passive"))
      (node (ref "J61") (pin "5") (pinfunction "5_5") (pintype "passive"))
    )
    (net (code "46") (name "Net-(J23-Pad1)") (class "Default")
      (node (ref "J23") (pin "1") (pinfunction "1_1") (pintype "passive"))
      (node (ref "J23") (pin "2") (pinfunction "2_2") (pintype "passive"))
      (node (ref "J23") (pin "3") (pinfunction "3_3") (pintype "passive"))
      (node (ref "J23") (pin "4") (pinfunction "4_4") (pintype "passive"))
      (node (ref "J23") (pin "5") (pinfunction "5_5") (pintype "passive"))
      (node (ref "J32") (pin "1") (pinfunction "1_1") (pintype "passive"))
      (node (ref "J32") (pin "2") (pinfunction "2_2") (pintype "passive"))
      (node (ref "J32") (pin "3") (pinfunction "3_3") (pintype "passive"))
      (node (ref "J32") (pin "4") (pinfunction "4_4") (pintype "passive"))
      (node (ref "J32") (pin "5") (pinfunction "5_5") (pintype "passive"))
    )
    (net (code "47") (name "Net-(J24-Pad1)") (class "Default")
      (node (ref "J24") (pin "1") (pinfunction "1_1") (pintype "passive"))
      (node (ref "J24") (pin "2") (pinfunction "2_2") (pintype "passive"))
      (node (ref "J24") (pin "3") (pinfunction "3_3") (pintype "passive"))
      (node (ref "J24") (pin "4") (pinfunction "4_4") (pintype "passive"))
      (node (ref "J24") (pin "5") (pinfunction "5_5") (pintype "passive"))
      (node (ref "J33") (pin "1") (pinfunction "1_1") (pintype "passive"))
      (node (ref "J33") (pin "2") (pinfunction "2_2") (pintype "passive"))
      (node (ref "J33") (pin "3") (pinfunction "3_3") (pintype "passive"))
      (node (ref "J33") (pin "4") (pinfunction "4_4") (pintype "passive"))
      (node (ref "J33") (pin "5") (pinfunction "5_5") (pintype "passive"))
    )
    (net (code "48") (name "Net-(J25-Pad1)") (class "Default")
      (node (ref "J25") (pin "1") (pinfunction "1_1") (pintype "passive"))
      (node (ref "J25") (pin "2") (pinfunction "2_2") (pintype "passive"))
      (node (ref "J25") (pin "3") (pinfunction "3_3") (pintype "passive"))
      (node (ref "J25") (pin "4") (pinfunction "4_4") (pintype "passive"))
      (node (ref "J25") (pin "5") (pinfunction "5_5") (pintype "passive"))
      (node (ref "J41") (pin "1") (pinfunction "1_1") (pintype "passive"))
      (node (ref "J41") (pin "2") (pinfunction "2_2") (pintype "passive"))
      (node (ref "J41") (pin "3") (pinfunction "3_3") (pintype "passive"))
      (node (ref "J41") (pin "4") (pinfunction "4_4") (pintype "passive"))
      (node (ref "J41") (pin "5") (pinfunction "5_5") (pintype "passive"))
    )
    (net (code "49") (name "Net-(J28-Pad1)") (class "Default")
      (node (ref "J28") (pin "1") (pinfunction "1_1") (pintype "passive"))
      (node (ref "J28") (pin "2") (pinfunction "2_2") (pintype "passive"))
      (node (ref "J28") (pin "3") (pinfunction "3_3") (pintype "passive"))
      (node (ref "J28") (pin "4") (pinfunction "4_4") (pintype "passive"))
      (node (ref "J28") (pin "5") (pinfunction "5_5") (pintype "passive"))
      (node (ref "J67") (pin "1") (pinfunction "1_1") (pintype "passive"))
      (node (ref "J67") (pin "2") (pinfunction "2_2") (pintype "passive"))
      (node (ref "J67") (pin "3") (pinfunction "3_3") (pintype "passive"))
      (node (ref "J67") (pin "4") (pinfunction "4_4") (pintype "passive"))
      (node (ref "J67") (pin "5") (pinfunction "5_5") (pintype "passive"))
    )
    (net (code "50") (name "Net-(J34-Pad1)") (class "Default")
      (node (ref "J34") (pin "1") (pinfunction "1_1") (pintype "passive"))
      (node (ref "J34") (pin "2") (pinfunction "2_2") (pintype "passive"))
      (node (ref "J34") (pin "3") (pinfunction "3_3") (pintype "passive"))
      (node (ref "J34") (pin "4") (pinfunction "4_4") (pintype "passive"))
      (node (ref "J34") (pin "5") (pinfunction "5_5") (pintype "passive"))
      (node (ref "J35") (pin "1") (pinfunction "1_1") (pintype "passive"))
      (node (ref "J35") (pin "2") (pinfunction "2_2") (pintype "passive"))
      (node (ref "J35") (pin "3") (pinfunction "3_3") (pintype "passive"))
      (node (ref "J35") (pin "4") (pinfunction "4_4") (pintype "passive"))
      (node (ref "J35") (pin "5") (pinfunction "5_5") (pintype "passive"))
    )
    (net (code "51") (name "Net-(J36-Pad1)") (class "Default")
      (node (ref "J36") (pin "1") (pinfunction "1_1") (pintype "passive"))
      (node (ref "J36") (pin "2") (pinfunction "2_2") (pintype "passive"))
      (node (ref "J36") (pin "3") (pinfunction "3_3") (pintype "passive"))
      (node (ref "J36") (pin "4") (pinfunction "4_4") (pintype "passive"))
      (node (ref "J36") (pin "5") (pinfunction "5_5") (pintype "passive"))
      (node (ref "J42") (pin "1") (pinfunction "1_1") (pintype "passive"))
      (node (ref "J42") (pin "2") (pinfunction "2_2") (pintype "passive"))
      (node (ref "J42") (pin "3") (pinfunction "3_3") (pintype "passive"))
      (node (ref "J42") (pin "4") (pinfunction "4_4") (pintype "passive"))
      (node (ref "J42") (pin "5") (pinfunction "5_5") (pintype "passive"))
    )
    (net (code "52") (name "Net-(J37-Pad1)") (class "Default")
      (node (ref "J37") (pin "1") (pinfunction "1_1") (pintype "passive"))
      (node (ref "J37") (pin "2") (pinfunction "2_2") (pintype "passive"))
      (node (ref "J37") (pin "3") (pinfunction "3_3") (pintype "passive"))
      (node (ref "J37") (pin "4") (pinfunction "4_4") (pintype "passive"))
      (node (ref "J37") (pin "5") (pinfunction "5_5") (pintype "passive"))
      (node (ref "J71") (pin "1") (pinfunction "1_1") (pintype "passive"))
      (node (ref "J71") (pin "2") (pinfunction "2_2") (pintype "passive"))
      (node (ref "J71") (pin "3") (pinfunction "3_3") (pintype "passive"))
      (node (ref "J71") (pin "4") (pinfunction "4_4") (pintype "passive"))
      (node (ref "J71") (pin "5") (pinfunction "5_5") (pintype "passive"))
    )
    (net (code "53") (name "Net-(J38-Pad1)") (class "Default")
      (node (ref "J38") (pin "1") (pinfunction "1_1") (pintype "passive"))
      (node (ref "J38") (pin "2") (pinfunction "2_2") (pintype "passive"))
      (node (ref "J38") (pin "3") (pinfunction "3_3") (pintype "passive"))
      (node (ref "J38") (pin "4") (pinfunction "4_4") (pintype "passive"))
      (node (ref "J38") (pin "5") (pinfunction "5_5") (pintype "passive"))
      (node (ref "J72") (pin "1") (pinfunction "1_1") (pintype "passive"))
      (node (ref "J72") (pin "2") (pinfunction "2_2") (pintype "passive"))
      (node (ref "J72") (pin "3") (pinfunction "3_3") (pintype "passive"))
      (node (ref "J72") (pin "4") (pinfunction "4_4") (pintype "passive"))
      (node (ref "J72") (pin "5") (pinfunction "5_5") (pintype "passive"))
    )
    (net (code "54") (name "Net-(J39-Pad1)") (class "Default")
      (node (ref "J39") (pin "1") (pinfunction "1_1") (pintype "passive"))
      (node (ref "J39") (pin "2") (pinfunction "2_2") (pintype "passive"))
      (node (ref "J39") (pin "3") (pinfunction "3_3") (pintype "passive"))
      (node (ref "J39") (pin "4") (pinfunction "4_4") (pintype "passive"))
      (node (ref "J39") (pin "5") (pinfunction "5_5") (pintype "passive"))
      (node (ref "J40") (pin "1") (pinfunction "1_1") (pintype "passive"))
      (node (ref "J40") (pin "2") (pinfunction "2_2") (pintype "passive"))
      (node (ref "J40") (pin "3") (pinfunction "3_3") (pintype "passive"))
      (node (ref "J40") (pin "4") (pinfunction "4_4") (pintype "passive"))
      (node (ref "J40") (pin "5") (pinfunction "5_5") (pintype "passive"))
    )
    (net (code "55") (name "Net-(J43-Pad1)") (class "Default")
      (node (ref "J43") (pin "1") (pinfunction "1_1") (pintype "passive"))
      (node (ref "J43") (pin "2") (pinfunction "2_2") (pintype "passive"))
      (node (ref "J43") (pin "3") (pinfunction "3_3") (pintype "passive"))
      (node (ref "J43") (pin "4") (pinfunction "4_4") (pintype "passive"))
      (node (ref "J43") (pin "5") (pinfunction "5_5") (pintype "passive"))
      (node (ref "J44") (pin "1") (pinfunction "1_1") (pintype "passive"))
      (node (ref "J44") (pin "2") (pinfunction "2_2") (pintype "passive"))
      (node (ref "J44") (pin "3") (pinfunction "3_3") (pintype "passive"))
      (node (ref "J44") (pin "4") (pinfunction "4_4") (pintype "passive"))
      (node (ref "J44") (pin "5") (pinfunction "5_5") (pintype "passive"))
    )
    (net (code "56") (name "Net-(J45-Pad1)") (class "Default")
      (node (ref "J45") (pin "1") (pinfunction "1_1") (pintype "passive"))
      (node (ref "J45") (pin "2") (pinfunction "2_2") (pintype "passive"))
      (node (ref "J45") (pin "3") (pinfunction "3_3") (pintype "passive"))
      (node (ref "J45") (pin "4") (pinfunction "4_4") (pintype "passive"))
      (node (ref "J45") (pin "5") (pinfunction "5_5") (pintype "passive"))
      (node (ref "J46") (pin "1") (pinfunction "1_1") (pintype "passive"))
      (node (ref "J46") (pin "2") (pinfunction "2_2") (pintype "passive"))
      (node (ref "J46") (pin "3") (pinfunction "3_3") (pintype "passive"))
      (node (ref "J46") (pin "4") (pinfunction "4_4") (pintype "passive"))
      (node (ref "J46") (pin "5") (pinfunction "5_5") (pintype "passive"))
    )
    (net (code "57") (name "Net-(J47-Pad1)") (class "Default")
      (node (ref "J47") (pin "1") (pinfunction "1_1") (pintype "passive"))
      (node (ref "J47") (pin "2") (pinfunction "2_2") (pintype "passive"))
      (node (ref "J47") (pin "3") (pinfunction "3_3") (pintype "passive"))
      (node (ref "J47") (pin "4") (pinfunction "4_4") (pintype "passive"))
      (node (ref "J47") (pin "5") (pinfunction "5_5") (pintype "passive"))
      (node (ref "J48") (pin "1") (pinfunction "1_1") (pintype "passive"))
      (node (ref "J48") (pin "2") (pinfunction "2_2") (pintype "passive"))
      (node (ref "J48") (pin "3") (pinfunction "3_3") (pintype "passive"))
      (node (ref "J48") (pin "4") (pinfunction "4_4") (pintype "passive"))
      (node (ref "J48") (pin "5") (pinfunction "5_5") (pintype "passive"))
    )
    (net (code "58") (name "Net-(J49-Pad1)") (class "Default")
      (node (ref "J49") (pin "1") (pinfunction "1_1") (pintype "passive"))
      (node (ref "J49") (pin "2") (pinfunction "2_2") (pintype "passive"))
      (node (ref "J49") (pin "3") (pinfunction "3_3") (pintype "passive"))
      (node (ref "J49") (pin "4") (pinfunction "4_4") (pintype "passive"))
      (node (ref "J49") (pin "5") (pinfunction "5_5") (pintype "passive"))
      (node (ref "J53") (pin "1") (pinfunction "1_1") (pintype "passive"))
      (node (ref "J53") (pin "2") (pinfunction "2_2") (pintype "passive"))
      (node (ref "J53") (pin "3") (pinfunction "3_3") (pintype "passive"))
      (node (ref "J53") (pin "4") (pinfunction "4_4") (pintype "passive"))
      (node (ref "J53") (pin "5") (pinfunction "5_5") (pintype "passive"))
    )
    (net (code "59") (name "Net-(J50-Pad1)") (class "Default")
      (node (ref "J50") (pin "1") (pinfunction "1_1") (pintype "passive"))
      (node (ref "J50") (pin "2") (pinfunction "2_2") (pintype "passive"))
      (node (ref "J50") (pin "3") (pinfunction "3_3") (pintype "passive"))
      (node (ref "J50") (pin "4") (pinfunction "4_4") (pintype "passive"))
      (node (ref "J50") (pin "5") (pinfunction "5_5") (pintype "passive"))
      (node (ref "J51") (pin "1") (pinfunction "1_1") (pintype "passive"))
      (node (ref "J51") (pin "2") (pinfunction "2_2") (pintype "passive"))
      (node (ref "J51") (pin "3") (pinfunction "3_3") (pintype "passive"))
      (node (ref "J51") (pin "4") (pinfunction "4_4") (pintype "passive"))
      (node (ref "J51") (pin "5") (pinfunction "5_5") (pintype "passive"))
    )
    (net (code "60") (name "Net-(J52-Pad1)") (class "Default")
      (node (ref "J52") (pin "1") (pinfunction "1_1") (pintype "passive"))
      (node (ref "J52") (pin "2") (pinfunction "2_2") (pintype "passive"))
      (node (ref "J52") (pin "3") (pinfunction "3_3") (pintype "passive"))
      (node (ref "J52") (pin "4") (pinfunction "4_4") (pintype "passive"))
      (node (ref "J52") (pin "5") (pinfunction "5_5") (pintype "passive"))
      (node (ref "J58") (pin "1") (pinfunction "1_1") (pintype "passive"))
      (node (ref "J58") (pin "2") (pinfunction "2_2") (pintype "passive"))
      (node (ref "J58") (pin "3") (pinfunction "3_3") (pintype "passive"))
      (node (ref "J58") (pin "4") (pinfunction "4_4") (pintype "passive"))
      (node (ref "J58") (pin "5") (pinfunction "5_5") (pintype "passive"))
    )
    (net (code "61") (name "Net-(J55-Pad1)") (class "Default")
      (node (ref "J55") (pin "1") (pinfunction "1_1") (pintype "passive"))
      (node (ref "J55") (pin "2") (pinfunction "2_2") (pintype "passive"))
      (node (ref "J55") (pin "3") (pinfunction "3_3") (pintype "passive"))
      (node (ref "J55") (pin "4") (pinfunction "4_4") (pintype "passive"))
      (node (ref "J55") (pin "5") (pinfunction "5_5") (pintype "passive"))
      (node (ref "J56") (pin "1") (pinfunction "1_1") (pintype "passive"))
      (node (ref "J56") (pin "2") (pinfunction "2_2") (pintype "passive"))
      (node (ref "J56") (pin "3") (pinfunction "3_3") (pintype "passive"))
      (node (ref "J56") (pin "4") (pinfunction "4_4") (pintype "passive"))
      (node (ref "J56") (pin "5") (pinfunction "5_5") (pintype "passive"))
    )
    (net (code "62") (name "Net-(J57-Pad1)") (class "Default")
      (node (ref "J57") (pin "1") (pinfunction "1_1") (pintype "passive"))
      (node (ref "J57") (pin "2") (pinfunction "2_2") (pintype "passive"))
      (node (ref "J57") (pin "3") (pinfunction "3_3") (pintype "passive"))
      (node (ref "J57") (pin "4") (pinfunction "4_4") (pintype "passive"))
      (node (ref "J57") (pin "5") (pinfunction "5_5") (pintype "passive"))
      (node (ref "J62") (pin "1") (pinfunction "1_1") (pintype "passive"))
      (node (ref "J62") (pin "2") (pinfunction "2_2") (pintype "passive"))
      (node (ref "J62") (pin "3") (pinfunction "3_3") (pintype "passive"))
      (node (ref "J62") (pin "4") (pinfunction "4_4") (pintype "passive"))
      (node (ref "J62") (pin "5") (pinfunction "5_5") (pintype "passive"))
    )
    (net (code "63") (name "Net-(J59-Pad1)") (class "Default")
      (node (ref "J59") (pin "1") (pinfunction "1_1") (pintype "passive"))
      (node (ref "J59") (pin "2") (pinfunction "2_2") (pintype "passive"))
      (node (ref "J59") (pin "3") (pinfunction "3_3") (pintype "passive"))
      (node (ref "J59") (pin "4") (pinfunction "4_4") (pintype "passive"))
      (node (ref "J59") (pin "5") (pinfunction "5_5") (pintype "passive"))
      (node (ref "J60") (pin "1") (pinfunction "1_1") (pintype "passive"))
      (node (ref "J60") (pin "2") (pinfunction "2_2") (pintype "passive"))
      (node (ref "J60") (pin "3") (pinfunction "3_3") (pintype "passive"))
      (node (ref "J60") (pin "4") (pinfunction "4_4") (pintype "passive"))
      (node (ref "J60") (pin "5") (pinfunction "5_5") (pintype "passive"))
    )
    (net (code "64") (name "Net-(J63-Pad1)") (class "Default")
      (node (ref "J63") (pin "1") (pinfunction "1_1") (pintype "passive"))
      (node (ref "J63") (pin "2") (pinfunction "2_2") (pintype "passive"))
      (node (ref "J63") (pin "3") (pinfunction "3_3") (pintype "passive"))
      (node (ref "J63") (pin "4") (pinfunction "4_4") (pintype "passive"))
      (node (ref "J63") (pin "5") (pinfunction "5_5") (pintype "passive"))
      (node (ref "J64") (pin "1") (pinfunction "1_1") (pintype "passive"))
      (node (ref "J64") (pin "2") (pinfunction "2_2") (pintype "passive"))
      (node (ref "J64") (pin "3") (pinfunction "3_3") (pintype "passive"))
      (node (ref "J64") (pin "4") (pinfunction "4_4") (pintype "passive"))
      (node (ref "J64") (pin "5") (pinfunction "5_5") (pintype "passive"))
    )
    (net (code "65") (name "Net-(J68-Pad1)") (class "Default")
      (node (ref "J68") (pin "1") (pinfunction "1_1") (pintype "passive"))
      (node (ref "J68") (pin "2") (pinfunction "2_2") (pintype "passive"))
      (node (ref "J68") (pin "3") (pinfunction "3_3") (pintype "passive"))
      (node (ref "J68") (pin "4") (pinfunction "4_4") (pintype "passive"))
      (node (ref "J68") (pin "5") (pinfunction "5_5") (pintype "passive"))
      (node (ref "J69") (pin "1") (pinfunction "1_1") (pintype "passive"))
      (node (ref "J69") (pin "2") (pinfunction "2_2") (pintype "passive"))
      (node (ref "J69") (pin "3") (pinfunction "3_3") (pintype "passive"))
      (node (ref "J69") (pin "4") (pinfunction "4_4") (pintype "passive"))
      (node (ref "J69") (pin "5") (pinfunction "5_5") (pintype "passive"))
    )
    (net (code "66") (name "Net-(J70-Pad1)") (class "Default")
      (node (ref "J70") (pin "1") (pinfunction "1_1") (pintype "passive"))
      (node (ref "J70") (pin "2") (pinfunction "2_2") (pintype "passive"))
      (node (ref "J70") (pin "3") (pinfunction "3_3") (pintype "passive"))
      (node (ref "J70") (pin "4") (pinfunction "4_4") (pintype "passive"))
      (node (ref "J70") (pin "5") (pinfunction "5_5") (pintype "passive"))
      (node (ref "J75") (pin "1") (pinfunction "1_1") (pintype "passive"))
      (node (ref "J75") (pin "2") (pinfunction "2_2") (pintype "passive"))
      (node (ref "J75") (pin "3") (pinfunction "3_3") (pintype "passive"))
      (node (ref "J75") (pin "4") (pinfunction "4_4") (pintype "passive"))
      (node (ref "J75") (pin "5") (pinfunction "5_5") (pintype "passive"))
    )
    (net (code "67") (name "Net-(J76-Pad1)") (class "Default")
      (node (ref "J76") (pin "1") (pinfunction "1_1") (pintype "passive"))
      (node (ref "J76") (pin "2") (pinfunction "2_2") (pintype "passive"))
      (node (ref "J76") (pin "3") (pinfunction "3_3") (pintype "passive"))
      (node (ref "J76") (pin "4") (pinfunction "4_4") (pintype "passive"))
      (node (ref "J76") (pin "5") (pinfunction "5_5") (pintype "passive"))
      (node (ref "J77") (pin "1") (pinfunction "1_1") (pintype "passive"))
      (node (ref "J77") (pin "2") (pinfunction "2_2") (pintype "passive"))
      (node (ref "J77") (pin "3") (pinfunction "3_3") (pintype "passive"))
      (node (ref "J77") (pin "4") (pinfunction "4_4") (pintype "passive"))
      (node (ref "J77") (pin "5") (pinfunction "5_5") (pintype "passive"))
    )
    (net (code "68") (name "Net-(J78-Pad1)") (class "Default")
      (node (ref "J78") (pin "1") (pinfunction "1_1") (pintype "passive"))
      (node (ref "J78") (pin "2") (pinfunction "2_2") (pintype "passive"))
      (node (ref "J78") (pin "3") (pinfunction "3_3") (pintype "passive"))
      (node (ref "J78") (pin "4") (pinfunction "4_4") (pintype "passive"))
      (node (ref "J78") (pin "5") (pinfunction "5_5") (pintype "passive"))
      (node (ref "J79") (pin "1") (pinfunction "1_1") (pintype "passive"))
      (node (ref "J79") (pin "2") (pinfunction "2_2") (pintype "passive"))
      (node (ref "J79") (pin "3") (pinfunction "3_3") (pintype "passive"))
      (node (ref "J79") (pin "4") (pinfunction "4_4") (pintype "passive"))
      (node (ref "J79") (pin "5") (pinfunction "5_5") (pintype "passive"))
    )
    (net (code "69") (name "Net-(J80-Pad1)") (class "Default")
      (node (ref "J80") (pin "1") (pinfunction "1_1") (pintype "passive"))
      (node (ref "J80") (pin "2") (pinfunction "2_2") (pintype "passive"))
      (node (ref "J80") (pin "3") (pinfunction "3_3") (pintype "passive"))
      (node (ref "J80") (pin "4") (pinfunction "4_4") (pintype "passive"))
      (node (ref "J80") (pin "5") (pinfunction "5_5") (pintype "passive"))
      (node (ref "J81") (pin "1") (pinfunction "1_1") (pintype "passive"))
      (node (ref "J81") (pin "2") (pinfunction "2_2") (pintype "passive"))
      (node (ref "J81") (pin "3") (pinfunction "3_3") (pintype "passive"))
      (node (ref "J81") (pin "4") (pinfunction "4_4") (pintype "passive"))
      (node (ref "J81") (pin "5") (pinfunction "5_5") (pintype "passive"))
    )
    (net (code "70") (name "Net-(J82-Pad1)") (class "Default")
      (node (ref "J82") (pin "1") (pinfunction "1_1") (pintype "passive"))
      (node (ref "J82") (pin "2") (pinfunction "2_2") (pintype "passive"))
      (node (ref "J82") (pin "3") (pinfunction "3_3") (pintype "passive"))
      (node (ref "J82") (pin "4") (pinfunction "4_4") (pintype "passive"))
      (node (ref "J82") (pin "5") (pinfunction "5_5") (pintype "passive"))
      (node (ref "J86") (pin "1") (pinfunction "1_1") (pintype "passive"))
      (node (ref "J86") (pin "2") (pinfunction "2_2") (pintype "passive"))
      (node (ref "J86") (pin "3") (pinfunction "3_3") (pintype "passive"))
      (node (ref "J86") (pin "4") (pinfunction "4_4") (pintype "passive"))
      (node (ref "J86") (pin "5") (pinfunction "5_5") (pintype "passive"))
    )
    (net (code "71") (name "Net-(U$1-C)") (class "Default")
      (node (ref "C2") (pin "+") (pinfunction "+_+") (pintype "passive"))
      (node (ref "U$1") (pin "1") (pinfunction "C_1") (pintype "passive"))
      (node (ref "U1") (pin "3") (pinfunction "IN_3") (pintype "input"))
    )
    (net (code "72") (name "Net-(U1-ADJ)") (class "Default")
      (node (ref "R2") (pin "1") (pinfunction "1_1") (pintype "passive"))
      (node (ref "R3") (pin "2") (pinfunction "2_2") (pintype "passive"))
      (node (ref "U1") (pin "1") (pinfunction "ADJ_1") (pintype "input"))
    )
    (net (code "73") (name "unconnected-(ATMEGA328P-ADC6-Pad19)") (class "Default")
      (node (ref "ATMEGA328P") (pin "19") (pinfunction "ADC6_19") (pintype "bidirectional"))
    )
    (net (code "74") (name "unconnected-(ATMEGA328P-ADC7-Pad22)") (class "Default")
      (node (ref "ATMEGA328P") (pin "22") (pinfunction "ADC7_22") (pintype "bidirectional"))
    )
    (net (code "75") (name "unconnected-(POWER-Pad8)") (class "Default")
      (node (ref "POWER") (pin "8") (pinfunction "8_8") (pintype "passive"))
    )
  )
)
